# Rev_B_Main_Board.net
KiCad netlist of a schematic drawn in EAGLE
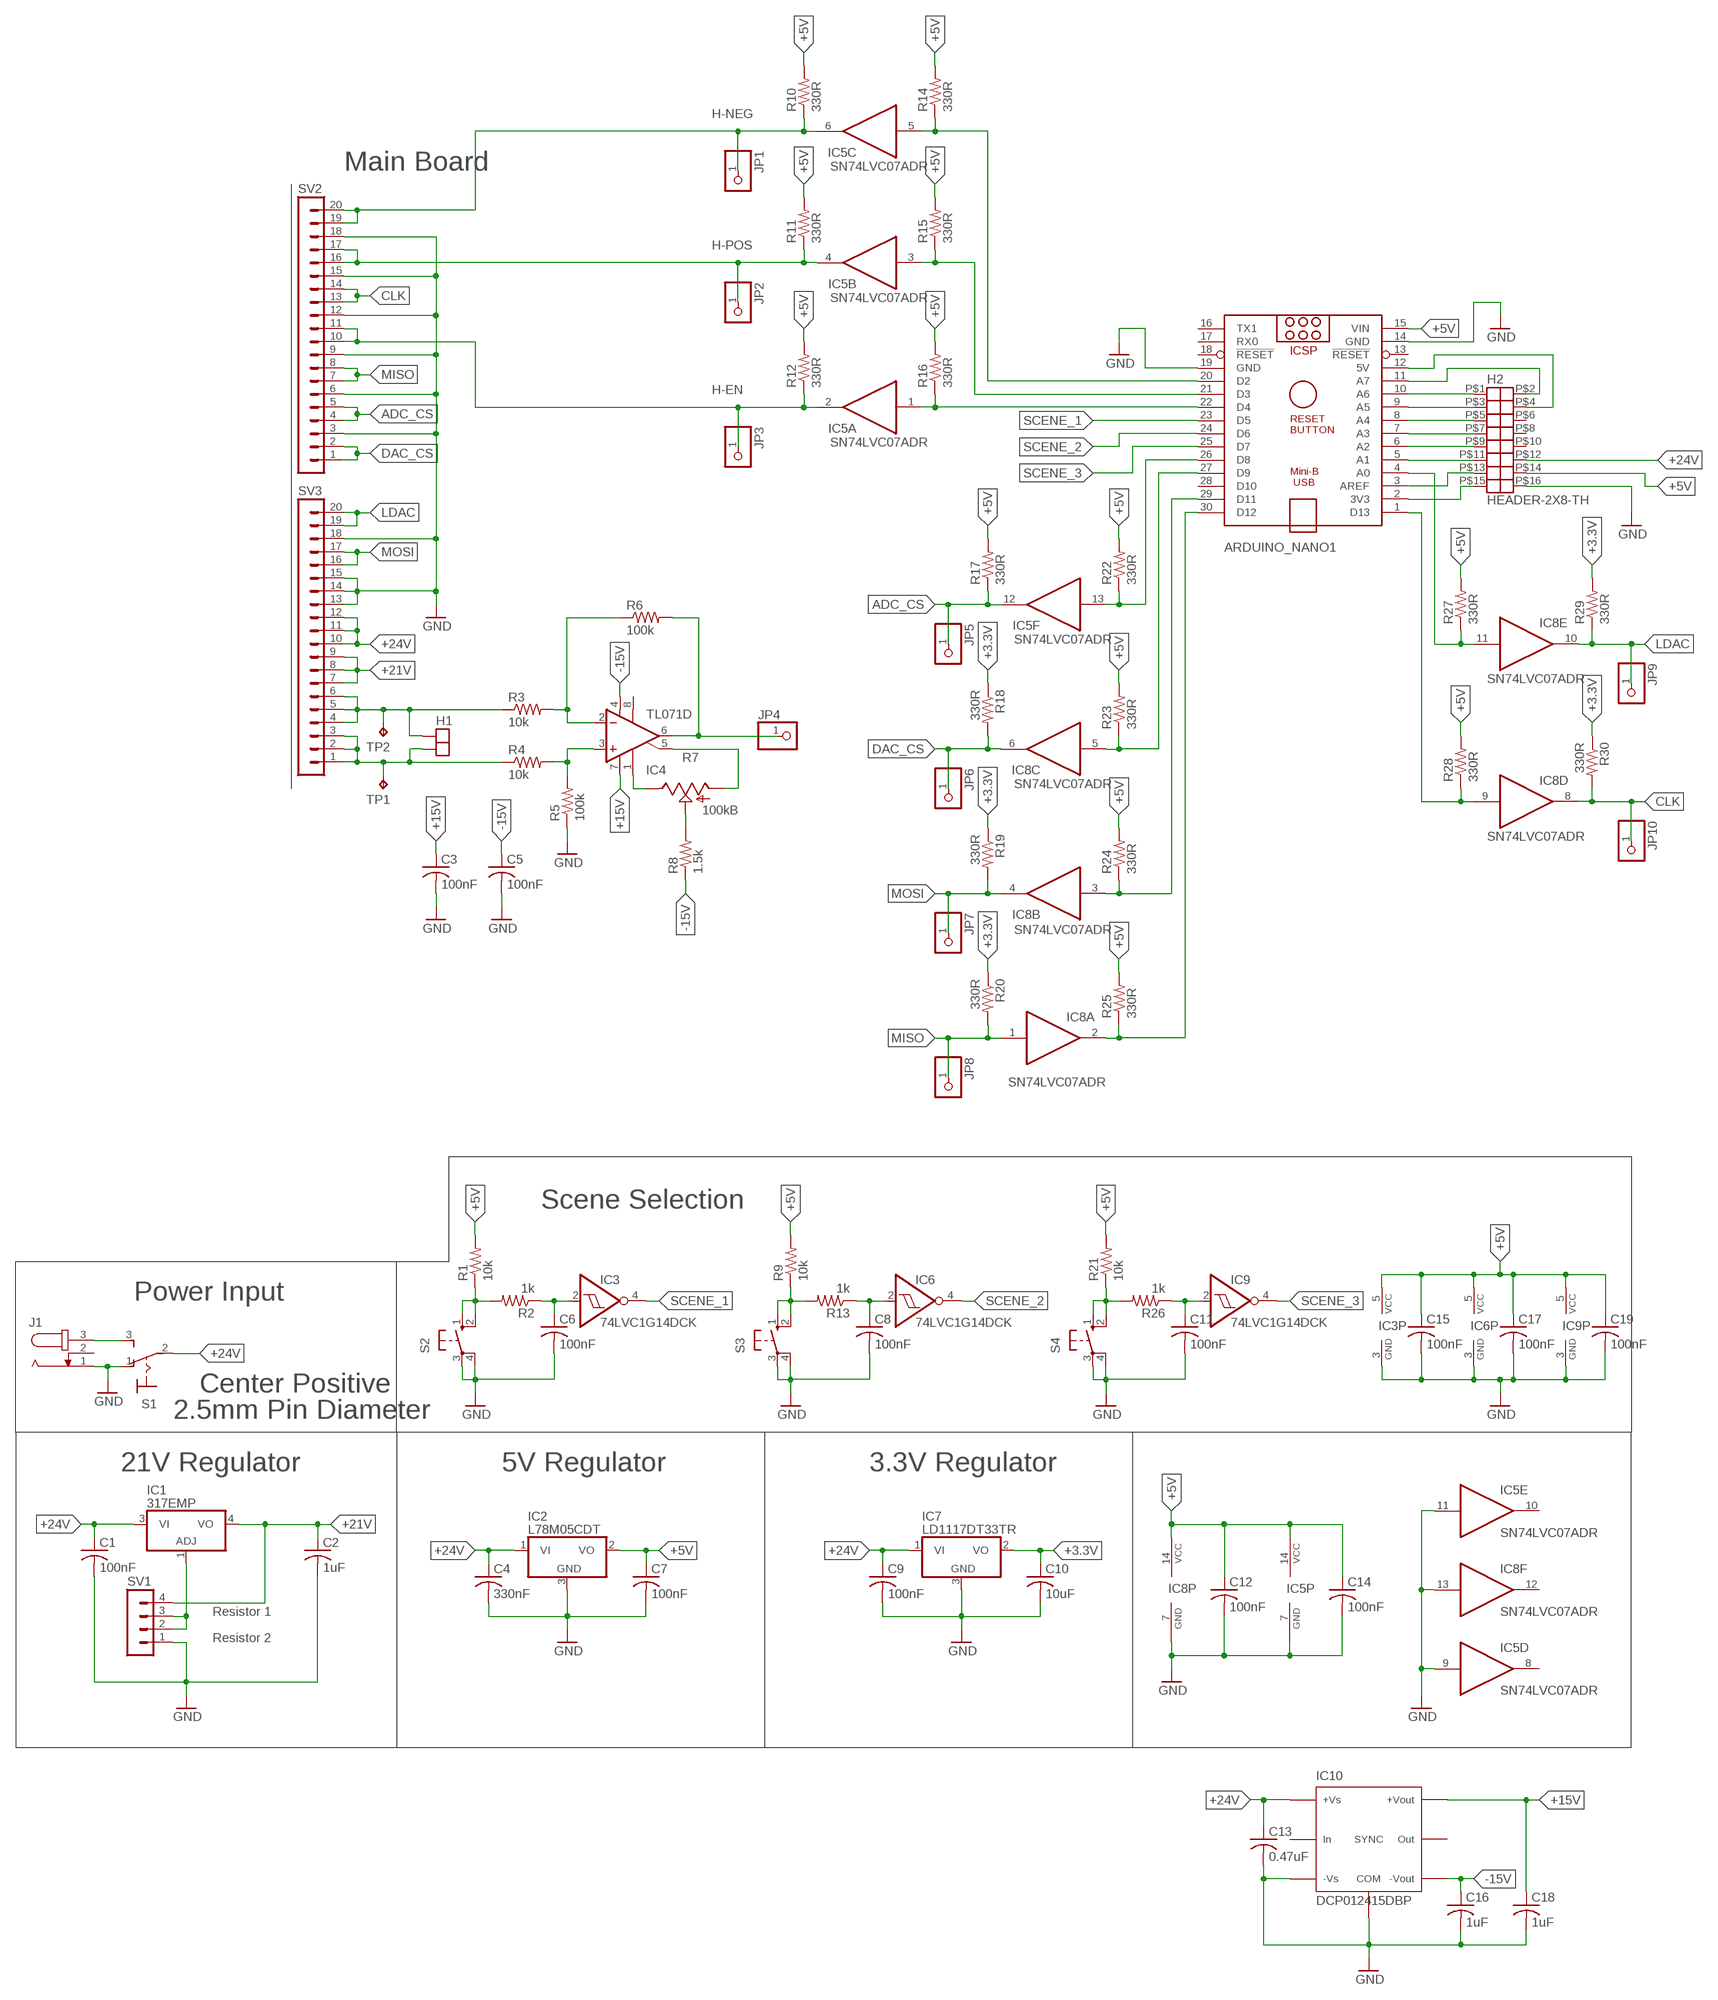
[diagram p0: schematic, sheet 1]

(export (version "E")
  (design (tool "Eeschema 10.0.6"))
  (components
    (comp (ref "ARDUINO_NANO1")
      (value "ARDUINO_NANO")
      (footprint "eagle-import:ARDUINO_NANO")
      (libsource (lib "eagle-import") (part "ARDUINO_NANO"))
    )
    (comp (ref "C1")
      (value "100nF")
      (footprint "eagle-import:C0805")
      (libsource (lib "eagle-import") (part "C-USC0805"))
    )
    (comp (ref "C2")
      (value "1uF")
      (footprint "eagle-import:C0805")
      (libsource (lib "eagle-import") (part "C-USC0805"))
    )
    (comp (ref "C3")
      (value "100nF")
      (footprint "eagle-import:C0805")
      (libsource (lib "eagle-import") (part "C-USC0805"))
    )
    (comp (ref "C4")
      (value "330nF")
      (footprint "eagle-import:C0805")
      (libsource (lib "eagle-import") (part "C-USC0805"))
    )
    (comp (ref "C5")
      (value "100nF")
      (footprint "eagle-import:C0805")
      (libsource (lib "eagle-import") (part "C-USC0805"))
    )
    (comp (ref "C6")
      (value "100nF")
      (footprint "eagle-import:C0805")
      (libsource (lib "eagle-import") (part "C-USC0805"))
    )
    (comp (ref "C7")
      (value "100nF")
      (footprint "eagle-import:C0805")
      (libsource (lib "eagle-import") (part "C-USC0805"))
    )
    (comp (ref "C8")
      (value "100nF")
      (footprint "eagle-import:C0805")
      (libsource (lib "eagle-import") (part "C-USC0805"))
    )
    (comp (ref "C9")
      (value "100nF")
      (footprint "eagle-import:C0805")
      (libsource (lib "eagle-import") (part "C-USC0805"))
    )
    (comp (ref "C10")
      (value "10uF")
      (footprint "eagle-import:C0805")
      (libsource (lib "eagle-import") (part "C-USC0805"))
    )
    (comp (ref "C11")
      (value "100nF")
      (footprint "eagle-import:C0805")
      (libsource (lib "eagle-import") (part "C-USC0805"))
    )
    (comp (ref "C12")
      (value "100nF")
      (footprint "eagle-import:C0805")
      (libsource (lib "eagle-import") (part "C-USC0805"))
    )
    (comp (ref "C13")
      (value "0.47uF")
      (footprint "eagle-import:C0805")
      (libsource (lib "eagle-import") (part "C-USC0805"))
    )
    (comp (ref "C14")
      (value "100nF")
      (footprint "eagle-import:C0805")
      (libsource (lib "eagle-import") (part "C-USC0805"))
    )
    (comp (ref "C15")
      (value "100nF")
      (footprint "eagle-import:C0805")
      (libsource (lib "eagle-import") (part "C-USC0805"))
    )
    (comp (ref "C16")
      (value "1uF")
      (footprint "eagle-import:C0805")
      (libsource (lib "eagle-import") (part "C-USC0805"))
    )
    (comp (ref "C17")
      (value "100nF")
      (footprint "eagle-import:C0805")
      (libsource (lib "eagle-import") (part "C-USC0805"))
    )
    (comp (ref "C18")
      (value "1uF")
      (footprint "eagle-import:C0805")
      (libsource (lib "eagle-import") (part "C-USC0805"))
    )
    (comp (ref "C19")
      (value "100nF")
      (footprint "eagle-import:C0805")
      (libsource (lib "eagle-import") (part "C-USC0805"))
    )
    (comp (ref "H1")
      (value "HEADER-1X2")
      (footprint "eagle-import:HEADER-1X2-TH")
      (libsource (lib "eagle-import") (part "HEADER-1X2"))
    )
    (comp (ref "H2")
      (value "HEADER-2X8-TH")
      (footprint "eagle-import:HEADER-2X8-TH")
      (libsource (lib "eagle-import") (part "HEADER-2X8-TH"))
    )
    (comp (ref "IC1")
      (value "317EMP")
      (footprint "eagle-import:SOT223")
      (libsource (lib "eagle-import") (part "317EMP"))
    )
    (comp (ref "IC2")
      (value "L78M05CDT")
      (footprint "eagle-import:TO252")
      (libsource (lib "eagle-import") (part "78DT18"))
    )
    (comp (ref "IC3")
      (value "74LVC1G14DCK")
      (footprint "eagle-import:SC70-5")
      (libsource (lib "eagle-import") (part "741G14DCKLVC"))
    )
    (comp (ref "IC4")
      (value "TL071D")
      (footprint "eagle-import:SO08")
      (libsource (lib "eagle-import") (part "TL071D"))
    )
    (comp (ref "IC5")
      (value "SN74LVC07ADR")
      (footprint "eagle-import:SO14")
      (libsource (lib "eagle-import") (part "7407DLS"))
    )
    (comp (ref "IC6")
      (value "74LVC1G14DCK")
      (footprint "eagle-import:SC70-5")
      (libsource (lib "eagle-import") (part "741G14DCKLVC"))
    )
    (comp (ref "IC7")
      (value "LD1117DT33TR")
      (footprint "eagle-import:TO252")
      (libsource (lib "eagle-import") (part "78DT18"))
    )
    (comp (ref "IC8")
      (value "SN74LVC07ADR")
      (footprint "eagle-import:SO14")
      (libsource (lib "eagle-import") (part "7407DLS"))
    )
    (comp (ref "IC9")
      (value "74LVC1G14DCK")
      (footprint "eagle-import:SC70-5")
      (libsource (lib "eagle-import") (part "741G14DCKLVC"))
    )
    (comp (ref "IC10")
      (value "DCP012415DBP")
      (footprint "eagle-import:7-PDIP")
      (libsource (lib "eagle-import") (part "DCP012415DBP"))
    )
    (comp (ref "J1")
      (value "JACK-PLUG1")
      (footprint "eagle-import:SPC4078")
      (libsource (lib "eagle-import") (part "JACK-PLUG1"))
    )
    (comp (ref "JP1")
      (value "PINHD-1X1")
      (footprint "eagle-import:1X01")
      (libsource (lib "eagle-import") (part "PINHD-1X1"))
    )
    (comp (ref "JP2")
      (value "PINHD-1X1")
      (footprint "eagle-import:1X01")
      (libsource (lib "eagle-import") (part "PINHD-1X1"))
    )
    (comp (ref "JP3")
      (value "PINHD-1X1")
      (footprint "eagle-import:1X01")
      (libsource (lib "eagle-import") (part "PINHD-1X1"))
    )
    (comp (ref "JP4")
      (value "PINHD-1X1")
      (footprint "eagle-import:1X01")
      (libsource (lib "eagle-import") (part "PINHD-1X1"))
    )
    (comp (ref "JP5")
      (value "PINHD-1X1")
      (footprint "eagle-import:1X01")
      (libsource (lib "eagle-import") (part "PINHD-1X1"))
    )
    (comp (ref "JP6")
      (value "PINHD-1X1")
      (footprint "eagle-import:1X01")
      (libsource (lib "eagle-import") (part "PINHD-1X1"))
    )
    (comp (ref "JP7")
      (value "PINHD-1X1")
      (footprint "eagle-import:1X01")
      (libsource (lib "eagle-import") (part "PINHD-1X1"))
    )
    (comp (ref "JP8")
      (value "PINHD-1X1")
      (footprint "eagle-import:1X01")
      (libsource (lib "eagle-import") (part "PINHD-1X1"))
    )
    (comp (ref "JP9")
      (value "PINHD-1X1")
      (footprint "eagle-import:1X01")
      (libsource (lib "eagle-import") (part "PINHD-1X1"))
    )
    (comp (ref "JP10")
      (value "PINHD-1X1")
      (footprint "eagle-import:1X01")
      (libsource (lib "eagle-import") (part "PINHD-1X1"))
    )
    (comp (ref "R1")
      (value "10k")
      (footprint "eagle-import:R0805")
      (libsource (lib "eagle-import") (part "R-US_R0805"))
    )
    (comp (ref "R2")
      (value "1k")
      (footprint "eagle-import:R0805")
      (libsource (lib "eagle-import") (part "R-US_R0805"))
    )
    (comp (ref "R3")
      (value "10k")
      (footprint "eagle-import:R0805")
      (libsource (lib "eagle-import") (part "R-US_R0805"))
    )
    (comp (ref "R4")
      (value "10k")
      (footprint "eagle-import:R0805")
      (libsource (lib "eagle-import") (part "R-US_R0805"))
    )
    (comp (ref "R5")
      (value "100k")
      (footprint "eagle-import:R0805")
      (libsource (lib "eagle-import") (part "R-US_R0805"))
    )
    (comp (ref "R6")
      (value "100k")
      (footprint "eagle-import:R0805")
      (libsource (lib "eagle-import") (part "R-US_R0805"))
    )
    (comp (ref "R7")
      (value "100kB")
      (footprint "eagle-import:RJ9W")
      (libsource (lib "eagle-import") (part "TRIM_US-RJ9W"))
    )
    (comp (ref "R8")
      (value "1.5k")
      (footprint "eagle-import:R0805")
      (libsource (lib "eagle-import") (part "R-US_R0805"))
    )
    (comp (ref "R9")
      (value "10k")
      (footprint "eagle-import:R0805")
      (libsource (lib "eagle-import") (part "R-US_R0805"))
    )
    (comp (ref "R10")
      (value "330R")
      (footprint "eagle-import:R0805")
      (libsource (lib "eagle-import") (part "R-US_R0805"))
    )
    (comp (ref "R11")
      (value "330R")
      (footprint "eagle-import:R0805")
      (libsource (lib "eagle-import") (part "R-US_R0805"))
    )
    (comp (ref "R12")
      (value "330R")
      (footprint "eagle-import:R0805")
      (libsource (lib "eagle-import") (part "R-US_R0805"))
    )
    (comp (ref "R13")
      (value "1k")
      (footprint "eagle-import:R0805")
      (libsource (lib "eagle-import") (part "R-US_R0805"))
    )
    (comp (ref "R14")
      (value "330R")
      (footprint "eagle-import:R0805")
      (libsource (lib "eagle-import") (part "R-US_R0805"))
    )
    (comp (ref "R15")
      (value "330R")
      (footprint "eagle-import:R0805")
      (libsource (lib "eagle-import") (part "R-US_R0805"))
    )
    (comp (ref "R16")
      (value "330R")
      (footprint "eagle-import:R0805")
      (libsource (lib "eagle-import") (part "R-US_R0805"))
    )
    (comp (ref "R17")
      (value "330R")
      (footprint "eagle-import:R0805")
      (libsource (lib "eagle-import") (part "R-US_R0805"))
    )
    (comp (ref "R18")
      (value "330R")
      (footprint "eagle-import:R0805")
      (libsource (lib "eagle-import") (part "R-US_R0805"))
    )
    (comp (ref "R19")
      (value "330R")
      (footprint "eagle-import:R0805")
      (libsource (lib "eagle-import") (part "R-US_R0805"))
    )
    (comp (ref "R20")
      (value "330R")
      (footprint "eagle-import:R0805")
      (libsource (lib "eagle-import") (part "R-US_R0805"))
    )
    (comp (ref "R21")
      (value "10k")
      (footprint "eagle-import:R0805")
      (libsource (lib "eagle-import") (part "R-US_R0805"))
    )
    (comp (ref "R22")
      (value "330R")
      (footprint "eagle-import:R0805")
      (libsource (lib "eagle-import") (part "R-US_R0805"))
    )
    (comp (ref "R23")
      (value "330R")
      (footprint "eagle-import:R0805")
      (libsource (lib "eagle-import") (part "R-US_R0805"))
    )
    (comp (ref "R24")
      (value "330R")
      (footprint "eagle-import:R0805")
      (libsource (lib "eagle-import") (part "R-US_R0805"))
    )
    (comp (ref "R25")
      (value "330R")
      (footprint "eagle-import:R0805")
      (libsource (lib "eagle-import") (part "R-US_R0805"))
    )
    (comp (ref "R26")
      (value "1k")
      (footprint "eagle-import:R0805")
      (libsource (lib "eagle-import") (part "R-US_R0805"))
    )
    (comp (ref "R27")
      (value "330R")
      (footprint "eagle-import:R0805")
      (libsource (lib "eagle-import") (part "R-US_R0805"))
    )
    (comp (ref "R28")
      (value "330R")
      (footprint "eagle-import:R0805")
      (libsource (lib "eagle-import") (part "R-US_R0805"))
    )
    (comp (ref "R29")
      (value "330R")
      (footprint "eagle-import:R0805")
      (libsource (lib "eagle-import") (part "R-US_R0805"))
    )
    (comp (ref "R30")
      (value "330R")
      (footprint "eagle-import:R0805")
      (libsource (lib "eagle-import") (part "R-US_R0805"))
    )
    (comp (ref "S1")
      (value "320-916")
      (footprint "eagle-import:320-916")
      (libsource (lib "eagle-import") (part "320-916"))
    )
    (comp (ref "S2")
      (value "10-XX")
      (footprint "eagle-import:B3F-10XX")
      (fields (field (name "MPN") "B3F-1000"))
      (libsource (lib "eagle-import") (part "10-XX"))
    )
    (comp (ref "S3")
      (value "10-XX")
      (footprint "eagle-import:B3F-10XX")
      (fields (field (name "MPN") "B3F-1000"))
      (libsource (lib "eagle-import") (part "10-XX"))
    )
    (comp (ref "S4")
      (value "10-XX")
      (footprint "eagle-import:B3F-10XX")
      (fields (field (name "MPN") "B3F-1000"))
      (libsource (lib "eagle-import") (part "10-XX"))
    )
    (comp (ref "SV1")
      (value "MA04-1")
      (footprint "eagle-import:MA04-1")
      (libsource (lib "eagle-import") (part "MA04-1"))
    )
    (comp (ref "SV2")
      (value "MA20-1W")
      (footprint "eagle-import:MA20-1W")
      (libsource (lib "eagle-import") (part "MA20-1W"))
    )
    (comp (ref "SV3")
      (value "MA20-1W")
      (footprint "eagle-import:MA20-1W")
      (libsource (lib "eagle-import") (part "MA20-1W"))
    )
    (comp (ref "TP1")
      (value "TPB2,54")
      (footprint "eagle-import:B2,54")
      (libsource (lib "eagle-import") (part "TPB2,54"))
    )
    (comp (ref "TP2")
      (value "TPB2,54")
      (footprint "eagle-import:B2,54")
      (libsource (lib "eagle-import") (part "TPB2,54"))
    )
  )
  (nets
    (net (code "1") (name "+3.3V") (class "Default")
      (node (ref "C10") (pin "1") (pinfunction "1_1") (pintype "passive"))
      (node (ref "IC7") (pin "2") (pinfunction "VO_2") (pintype "passive"))
      (node (ref "R18") (pin "1") (pinfunction "1_1") (pintype "passive"))
      (node (ref "R19") (pin "1") (pinfunction "1_1") (pintype "passive"))
      (node (ref "R20") (pin "1") (pinfunction "1_1") (pintype "passive"))
      (node (ref "R29") (pin "2") (pinfunction "2_2") (pintype "passive"))
      (node (ref "R30") (pin "1") (pinfunction "1_1") (pintype "passive"))
    )
    (net (code "2") (name "+5V") (class "Default")
      (node (ref "ARDUINO_NANO1") (pin "15") (pinfunction "VIN_15") (pintype "power_in"))
      (node (ref "C12") (pin "1") (pinfunction "1_1") (pintype "passive"))
      (node (ref "C14") (pin "1") (pinfunction "1_1") (pintype "passive"))
      (node (ref "C15") (pin "1") (pinfunction "1_1") (pintype "passive"))
      (node (ref "C17") (pin "1") (pinfunction "1_1") (pintype "passive"))
      (node (ref "C19") (pin "1") (pinfunction "1_1") (pintype "passive"))
      (node (ref "C7") (pin "1") (pinfunction "1_1") (pintype "passive"))
      (node (ref "H2") (pin "P$14") (pinfunction "P$14_P$14") (pintype "bidirectional"))
      (node (ref "IC2") (pin "2") (pinfunction "VO_2") (pintype "passive"))
      (node (ref "IC3") (pin "5") (pinfunction "VCC_5") (pintype "power_in"))
      (node (ref "IC5") (pin "14") (pinfunction "VCC_14") (pintype "power_in"))
      (node (ref "IC6") (pin "5") (pinfunction "VCC_5") (pintype "power_in"))
      (node (ref "IC8") (pin "14") (pinfunction "VCC_14") (pintype "power_in"))
      (node (ref "IC9") (pin "5") (pinfunction "VCC_5") (pintype "power_in"))
      (node (ref "R1") (pin "2") (pinfunction "2_2") (pintype "passive"))
      (node (ref "R10") (pin "2") (pinfunction "2_2") (pintype "passive"))
      (node (ref "R11") (pin "2") (pinfunction "2_2") (pintype "passive"))
      (node (ref "R12") (pin "2") (pinfunction "2_2") (pintype "passive"))
      (node (ref "R14") (pin "2") (pinfunction "2_2") (pintype "passive"))
      (node (ref "R15") (pin "2") (pinfunction "2_2") (pintype "passive"))
      (node (ref "R16") (pin "2") (pinfunction "2_2") (pintype "passive"))
      (node (ref "R17") (pin "2") (pinfunction "2_2") (pintype "passive"))
      (node (ref "R21") (pin "2") (pinfunction "2_2") (pintype "passive"))
      (node (ref "R22") (pin "2") (pinfunction "2_2") (pintype "passive"))
      (node (ref "R23") (pin "2") (pinfunction "2_2") (pintype "passive"))
      (node (ref "R24") (pin "2") (pinfunction "2_2") (pintype "passive"))
      (node (ref "R25") (pin "2") (pinfunction "2_2") (pintype "passive"))
      (node (ref "R27") (pin "2") (pinfunction "2_2") (pintype "passive"))
      (node (ref "R28") (pin "2") (pinfunction "2_2") (pintype "passive"))
      (node (ref "R9") (pin "2") (pinfunction "2_2") (pintype "passive"))
    )
    (net (code "3") (name "+15V") (class "Default")
      (node (ref "C18") (pin "1") (pinfunction "1_1") (pintype "passive"))
      (node (ref "C3") (pin "1") (pinfunction "1_1") (pintype "passive"))
      (node (ref "IC10") (pin "P$4") (pinfunction "P$4_P$4") (pintype "bidirectional"))
      (node (ref "IC4") (pin "7") (pinfunction "V+_7") (pintype "power_in"))
    )
    (net (code "4") (name "+21V") (class "Default")
      (node (ref "C2") (pin "1") (pinfunction "1_1") (pintype "passive"))
      (node (ref "IC1") (pin "4") (pinfunction "VO_4") (pintype "passive"))
      (node (ref "SV1") (pin "4") (pinfunction "4_4") (pintype "passive"))
      (node (ref "SV3") (pin "7") (pinfunction "7_7") (pintype "passive"))
      (node (ref "SV3") (pin "8") (pinfunction "8_8") (pintype "passive"))
      (node (ref "SV3") (pin "9") (pinfunction "9_9") (pintype "passive"))
    )
    (net (code "5") (name "+24V") (class "Default")
      (node (ref "C1") (pin "1") (pinfunction "1_1") (pintype "passive"))
      (node (ref "C13") (pin "1") (pinfunction "1_1") (pintype "passive"))
      (node (ref "C4") (pin "1") (pinfunction "1_1") (pintype "passive"))
      (node (ref "C9") (pin "1") (pinfunction "1_1") (pintype "passive"))
      (node (ref "H2") (pin "P$12") (pinfunction "P$12_P$12") (pintype "bidirectional"))
      (node (ref "IC1") (pin "3") (pinfunction "VI_3") (pintype "input"))
      (node (ref "IC10") (pin "P$1") (pinfunction "P$1_P$1") (pintype "bidirectional"))
      (node (ref "IC2") (pin "1") (pinfunction "VI_1") (pintype "input"))
      (node (ref "IC7") (pin "1") (pinfunction "VI_1") (pintype "input"))
      (node (ref "S1") (pin "2") (pinfunction "P_2") (pintype "passive"))
      (node (ref "SV3") (pin "10") (pinfunction "10_10") (pintype "passive"))
      (node (ref "SV3") (pin "11") (pinfunction "11_11") (pintype "passive"))
      (node (ref "SV3") (pin "12") (pinfunction "12_12") (pintype "passive"))
    )
    (net (code "6") (name "-15V") (class "Default")
      (node (ref "C16") (pin "1") (pinfunction "1_1") (pintype "passive"))
      (node (ref "C5") (pin "1") (pinfunction "1_1") (pintype "passive"))
      (node (ref "IC10") (pin "P$5") (pinfunction "P$5_P$5") (pintype "bidirectional"))
      (node (ref "IC4") (pin "4") (pinfunction "V-_4") (pintype "power_in"))
      (node (ref "R8") (pin "1") (pinfunction "1_1") (pintype "passive"))
    )
    (net (code "7") (name "ADC_CS") (class "Default")
      (node (ref "IC5") (pin "12") (pinfunction "O_12") (pintype "open_collector"))
      (node (ref "JP5") (pin "1") (pinfunction "1_1") (pintype "passive"))
      (node (ref "R17") (pin "1") (pinfunction "1_1") (pintype "passive"))
      (node (ref "SV2") (pin "4") (pinfunction "4_4") (pintype "passive"))
      (node (ref "SV2") (pin "5") (pinfunction "5_5") (pintype "passive"))
    )
    (net (code "8") (name "CLK") (class "Default")
      (node (ref "IC8") (pin "8") (pinfunction "O_8") (pintype "open_collector"))
      (node (ref "JP10") (pin "1") (pinfunction "1_1") (pintype "passive"))
      (node (ref "R30") (pin "2") (pinfunction "2_2") (pintype "passive"))
      (node (ref "SV2") (pin "13") (pinfunction "13_13") (pintype "passive"))
      (node (ref "SV2") (pin "14") (pinfunction "14_14") (pintype "passive"))
    )
    (net (code "9") (name "DAC_CS") (class "Default")
      (node (ref "IC8") (pin "6") (pinfunction "O_6") (pintype "open_collector"))
      (node (ref "JP6") (pin "1") (pinfunction "1_1") (pintype "passive"))
      (node (ref "R18") (pin "2") (pinfunction "2_2") (pintype "passive"))
      (node (ref "SV2") (pin "1") (pinfunction "1_1") (pintype "passive"))
      (node (ref "SV2") (pin "2") (pinfunction "2_2") (pintype "passive"))
    )
    (net (code "10") (name "GND") (class "Default")
      (node (ref "ARDUINO_NANO1") (pin "14") (pinfunction "GND_14") (pintype "power_in"))
      (node (ref "ARDUINO_NANO1") (pin "19") (pinfunction "GND_19") (pintype "power_in"))
      (node (ref "C1") (pin "2") (pinfunction "2_2") (pintype "passive"))
      (node (ref "C10") (pin "2") (pinfunction "2_2") (pintype "passive"))
      (node (ref "C11") (pin "2") (pinfunction "2_2") (pintype "passive"))
      (node (ref "C12") (pin "2") (pinfunction "2_2") (pintype "passive"))
      (node (ref "C13") (pin "2") (pinfunction "2_2") (pintype "passive"))
      (node (ref "C14") (pin "2") (pinfunction "2_2") (pintype "passive"))
      (node (ref "C15") (pin "2") (pinfunction "2_2") (pintype "passive"))
      (node (ref "C16") (pin "2") (pinfunction "2_2") (pintype "passive"))
      (node (ref "C17") (pin "2") (pinfunction "2_2") (pintype "passive"))
      (node (ref "C18") (pin "2") (pinfunction "2_2") (pintype "passive"))
      (node (ref "C19") (pin "2") (pinfunction "2_2") (pintype "passive"))
      (node (ref "C2") (pin "2") (pinfunction "2_2") (pintype "passive"))
      (node (ref "C3") (pin "2") (pinfunction "2_2") (pintype "passive"))
      (node (ref "C4") (pin "2") (pinfunction "2_2") (pintype "passive"))
      (node (ref "C5") (pin "2") (pinfunction "2_2") (pintype "passive"))
      (node (ref "C6") (pin "2") (pinfunction "2_2") (pintype "passive"))
      (node (ref "C7") (pin "2") (pinfunction "2_2") (pintype "passive"))
      (node (ref "C8") (pin "2") (pinfunction "2_2") (pintype "passive"))
      (node (ref "C9") (pin "2") (pinfunction "2_2") (pintype "passive"))
      (node (ref "H2") (pin "P$16") (pinfunction "P$16_P$16") (pintype "bidirectional"))
      (node (ref "IC10") (pin "P$2") (pinfunction "P$3_P$2") (pintype "bidirectional"))
      (node (ref "IC10") (pin "P$3") (pinfunction "P$7_P$3") (pintype "bidirectional"))
      (node (ref "IC2") (pin "3") (pinfunction "GND_3") (pintype "passive"))
      (node (ref "IC3") (pin "3") (pinfunction "GND_3") (pintype "power_in"))
      (node (ref "IC5") (pin "11") (pinfunction "I_11") (pintype "input"))
      (node (ref "IC5") (pin "7") (pinfunction "GND_7") (pintype "power_in"))
      (node (ref "IC5") (pin "9") (pinfunction "I_9") (pintype "input"))
      (node (ref "IC6") (pin "3") (pinfunction "GND_3") (pintype "power_in"))
      (node (ref "IC7") (pin "3") (pinfunction "GND_3") (pintype "passive"))
      (node (ref "IC8") (pin "13") (pinfunction "I_13") (pintype "input"))
      (node (ref "IC8") (pin "7") (pinfunction "GND_7") (pintype "power_in"))
      (node (ref "IC9") (pin "3") (pinfunction "GND_3") (pintype "power_in"))
      (node (ref "J1") (pin "1") (pinfunction "1_1") (pintype "passive"))
      (node (ref "R5") (pin "1") (pinfunction "1_1") (pintype "passive"))
      (node (ref "S1") (pin "1") (pinfunction "O_1") (pintype "passive"))
      (node (ref "S2") (pin "3") (pinfunction "P_3") (pintype "passive"))
      (node (ref "S2") (pin "4") (pinfunction "P1_4") (pintype "passive"))
      (node (ref "S3") (pin "3") (pinfunction "P_3") (pintype "passive"))
      (node (ref "S3") (pin "4") (pinfunction "P1_4") (pintype "passive"))
      (node (ref "S4") (pin "3") (pinfunction "P_3") (pintype "passive"))
      (node (ref "S4") (pin "4") (pinfunction "P1_4") (pintype "passive"))
      (node (ref "SV1") (pin "1") (pinfunction "1_1") (pintype "passive"))
      (node (ref "SV2") (pin "12") (pinfunction "12_12") (pintype "passive"))
      (node (ref "SV2") (pin "15") (pinfunction "15_15") (pintype "passive"))
      (node (ref "SV2") (pin "18") (pinfunction "18_18") (pintype "passive"))
      (node (ref "SV2") (pin "3") (pinfunction "3_3") (pintype "passive"))
      (node (ref "SV2") (pin "6") (pinfunction "6_6") (pintype "passive"))
      (node (ref "SV2") (pin "9") (pinfunction "9_9") (pintype "passive"))
      (node (ref "SV3") (pin "13") (pinfunction "13_13") (pintype "passive"))
      (node (ref "SV3") (pin "14") (pinfunction "14_14") (pintype "passive"))
      (node (ref "SV3") (pin "15") (pinfunction "15_15") (pintype "passive"))
      (node (ref "SV3") (pin "18") (pinfunction "18_18") (pintype "passive"))
    )
    (net (code "11") (name "LDAC") (class "Default")
      (node (ref "IC8") (pin "10") (pinfunction "O_10") (pintype "open_collector"))
      (node (ref "JP9") (pin "1") (pinfunction "1_1") (pintype "passive"))
      (node (ref "R29") (pin "1") (pinfunction "1_1") (pintype "passive"))
      (node (ref "SV3") (pin "19") (pinfunction "19_19") (pintype "passive"))
      (node (ref "SV3") (pin "20") (pinfunction "20_20") (pintype "passive"))
    )
    (net (code "12") (name "MISO") (class "Default")
      (node (ref "IC8") (pin "1") (pinfunction "I_1") (pintype "input"))
      (node (ref "JP8") (pin "1") (pinfunction "1_1") (pintype "passive"))
      (node (ref "R20") (pin "2") (pinfunction "2_2") (pintype "passive"))
      (node (ref "SV2") (pin "7") (pinfunction "7_7") (pintype "passive"))
      (node (ref "SV2") (pin "8") (pinfunction "8_8") (pintype "passive"))
    )
    (net (code "13") (name "MOSI") (class "Default")
      (node (ref "IC8") (pin "4") (pinfunction "O_4") (pintype "open_collector"))
      (node (ref "JP7") (pin "1") (pinfunction "1_1") (pintype "passive"))
      (node (ref "R19") (pin "2") (pinfunction "2_2") (pintype "passive"))
      (node (ref "SV3") (pin "16") (pinfunction "16_16") (pintype "passive"))
      (node (ref "SV3") (pin "17") (pinfunction "17_17") (pintype "passive"))
    )
    (net (code "14") (name "Net-(ARDUINO_NANO1-3V3)") (class "Default")
      (node (ref "ARDUINO_NANO1") (pin "2") (pinfunction "3V3_2") (pintype "output"))
      (node (ref "H2") (pin "P$15") (pinfunction "P$15_P$15") (pintype "bidirectional"))
    )
    (net (code "15") (name "Net-(ARDUINO_NANO1-5V)") (class "Default")
      (node (ref "ARDUINO_NANO1") (pin "12") (pinfunction "5V_12") (pintype "power_in"))
      (node (ref "H2") (pin "P$4") (pinfunction "P$4_P$4") (pintype "bidirectional"))
    )
    (net (code "16") (name "Net-(ARDUINO_NANO1-A0)") (class "Default")
      (node (ref "ARDUINO_NANO1") (pin "4") (pinfunction "A0_4") (pintype "bidirectional"))
      (node (ref "IC8") (pin "11") (pinfunction "I_11") (pintype "input"))
      (node (ref "R27") (pin "1") (pinfunction "1_1") (pintype "passive"))
    )
    (net (code "17") (name "Net-(ARDUINO_NANO1-A1)") (class "Default")
      (node (ref "ARDUINO_NANO1") (pin "5") (pinfunction "A1_5") (pintype "bidirectional"))
      (node (ref "H2") (pin "P$11") (pinfunction "P$11_P$11") (pintype "bidirectional"))
    )
    (net (code "18") (name "Net-(ARDUINO_NANO1-A2)") (class "Default")
      (node (ref "ARDUINO_NANO1") (pin "6") (pinfunction "A2_6") (pintype "bidirectional"))
      (node (ref "H2") (pin "P$9") (pinfunction "P$9_P$9") (pintype "bidirectional"))
    )
    (net (code "19") (name "Net-(ARDUINO_NANO1-A3)") (class "Default")
      (node (ref "ARDUINO_NANO1") (pin "7") (pinfunction "A3_7") (pintype "bidirectional"))
      (node (ref "H2") (pin "P$7") (pinfunction "P$7_P$7") (pintype "bidirectional"))
    )
    (net (code "20") (name "Net-(ARDUINO_NANO1-A4)") (class "Default")
      (node (ref "ARDUINO_NANO1") (pin "8") (pinfunction "A4_8") (pintype "bidirectional"))
      (node (ref "H2") (pin "P$5") (pinfunction "P$5_P$5") (pintype "bidirectional"))
    )
    (net (code "21") (name "Net-(ARDUINO_NANO1-A5)") (class "Default")
      (node (ref "ARDUINO_NANO1") (pin "9") (pinfunction "A5_9") (pintype "bidirectional"))
      (node (ref "H2") (pin "P$3") (pinfunction "P$3_P$3") (pintype "bidirectional"))
    )
    (net (code "22") (name "Net-(ARDUINO_NANO1-A6)") (class "Default")
      (node (ref "ARDUINO_NANO1") (pin "10") (pinfunction "A6_10") (pintype "bidirectional"))
      (node (ref "H2") (pin "P$1") (pinfunction "P$1_P$1") (pintype "bidirectional"))
    )
    (net (code "23") (name "Net-(ARDUINO_NANO1-A7)") (class "Default")
      (node (ref "ARDUINO_NANO1") (pin "11") (pinfunction "A7_11") (pintype "bidirectional"))
      (node (ref "H2") (pin "P$2") (pinfunction "P$2_P$2") (pintype "bidirectional"))
    )
    (net (code "24") (name "Net-(ARDUINO_NANO1-AREF)") (class "Default")
      (node (ref "ARDUINO_NANO1") (pin "3") (pinfunction "AREF_3") (pintype "input"))
      (node (ref "H2") (pin "P$13") (pinfunction "P$13_P$13") (pintype "bidirectional"))
    )
    (net (code "25") (name "Net-(ARDUINO_NANO1-D2)") (class "Default")
      (node (ref "ARDUINO_NANO1") (pin "20") (pinfunction "D2_20") (pintype "bidirectional"))
      (node (ref "IC5") (pin "5") (pinfunction "I_5") (pintype "input"))
      (node (ref "R14") (pin "1") (pinfunction "1_1") (pintype "passive"))
    )
    (net (code "26") (name "Net-(ARDUINO_NANO1-D3)") (class "Default")
      (node (ref "ARDUINO_NANO1") (pin "21") (pinfunction "D3_21") (pintype "bidirectional"))
      (node (ref "IC5") (pin "3") (pinfunction "I_3") (pintype "input"))
      (node (ref "R15") (pin "1") (pinfunction "1_1") (pintype "passive"))
    )
    (net (code "27") (name "Net-(ARDUINO_NANO1-D4)") (class "Default")
      (node (ref "ARDUINO_NANO1") (pin "22") (pinfunction "D4_22") (pintype "bidirectional"))
      (node (ref "IC5") (pin "1") (pinfunction "I_1") (pintype "input"))
      (node (ref "R16") (pin "1") (pinfunction "1_1") (pintype "passive"))
    )
    (net (code "28") (name "Net-(ARDUINO_NANO1-D8)") (class "Default")
      (node (ref "ARDUINO_NANO1") (pin "26") (pinfunction "D8_26") (pintype "bidirectional"))
      (node (ref "IC5") (pin "13") (pinfunction "I_13") (pintype "input"))
      (node (ref "R22") (pin "1") (pinfunction "1_1") (pintype "passive"))
    )
    (net (code "29") (name "Net-(ARDUINO_NANO1-D9)") (class "Default")
      (node (ref "ARDUINO_NANO1") (pin "27") (pinfunction "D9_27") (pintype "bidirectional"))
      (node (ref "IC8") (pin "5") (pinfunction "I_5") (pintype "input"))
      (node (ref "R23") (pin "1") (pinfunction "1_1") (pintype "passive"))
    )
    (net (code "30") (name "Net-(ARDUINO_NANO1-D11)") (class "Default")
      (node (ref "ARDUINO_NANO1") (pin "29") (pinfunction "D11_29") (pintype "bidirectional"))
      (node (ref "IC8") (pin "3") (pinfunction "I_3") (pintype "input"))
      (node (ref "R24") (pin "1") (pinfunction "1_1") (pintype "passive"))
    )
    (net (code "31") (name "Net-(ARDUINO_NANO1-D12)") (class "Default")
      (node (ref "ARDUINO_NANO1") (pin "30") (pinfunction "D12_30") (pintype "bidirectional"))
      (node (ref "IC8") (pin "2") (pinfunction "O_2") (pintype "open_collector"))
      (node (ref "R25") (pin "1") (pinfunction "1_1") (pintype "passive"))
    )
    (net (code "32") (name "Net-(ARDUINO_NANO1-D13)") (class "Default")
      (node (ref "ARDUINO_NANO1") (pin "1") (pinfunction "D13_1") (pintype "bidirectional"))
      (node (ref "IC8") (pin "9") (pinfunction "I_9") (pintype "input"))
      (node (ref "R28") (pin "1") (pinfunction "1_1") (pintype "passive"))
    )
    (net (code "33") (name "Net-(H1-PadP$1)") (class "Default")
      (node (ref "H1") (pin "P$1") (pinfunction "P$1_P$1") (pintype "bidirectional"))
      (node (ref "R3") (pin "1") (pinfunction "1_1") (pintype "passive"))
      (node (ref "SV3") (pin "4") (pinfunction "4_4") (pintype "passive"))
      (node (ref "SV3") (pin "5") (pinfunction "5_5") (pintype "passive"))
      (node (ref "SV3") (pin "6") (pinfunction "6_6") (pintype "passive"))
      (node (ref "TP2") (pin "TP") (pinfunction "TP_TP") (pintype "input"))
    )
    (net (code "34") (name "Net-(H1-PadP$2)") (class "Default")
      (node (ref "H1") (pin "P$2") (pinfunction "P$2_P$2") (pintype "bidirectional"))
      (node (ref "R4") (pin "1") (pinfunction "1_1") (pintype "passive"))
      (node (ref "SV3") (pin "1") (pinfunction "1_1") (pintype "passive"))
      (node (ref "SV3") (pin "2") (pinfunction "2_2") (pintype "passive"))
      (node (ref "SV3") (pin "3") (pinfunction "3_3") (pintype "passive"))
      (node (ref "TP1") (pin "TP") (pinfunction "TP_TP") (pintype "input"))
    )
    (net (code "35") (name "Net-(IC1-ADJ)") (class "Default")
      (node (ref "IC1") (pin "1") (pinfunction "ADJ_1") (pintype "input"))
      (node (ref "SV1") (pin "2") (pinfunction "2_2") (pintype "passive"))
      (node (ref "SV1") (pin "3") (pinfunction "3_3") (pintype "passive"))
    )
    (net (code "36") (name "Net-(IC3A-I)") (class "Default")
      (node (ref "C6") (pin "1") (pinfunction "1_1") (pintype "passive"))
      (node (ref "IC3") (pin "2") (pinfunction "I_2") (pintype "input"))
      (node (ref "R2") (pin "1") (pinfunction "1_1") (pintype "passive"))
    )
    (net (code "37") (name "Net-(IC4-+IN)") (class "Default")
      (node (ref "IC4") (pin "3") (pinfunction "+IN_3") (pintype "input"))
      (node (ref "R4") (pin "2") (pinfunction "2_2") (pintype "passive"))
      (node (ref "R5") (pin "2") (pinfunction "2_2") (pintype "passive"))
    )
    (net (code "38") (name "Net-(IC4--IN)") (class "Default")
      (node (ref "IC4") (pin "2") (pinfunction "-IN_2") (pintype "input"))
      (node (ref "R3") (pin "2") (pinfunction "2_2") (pintype "passive"))
      (node (ref "R6") (pin "1") (pinfunction "1_1") (pintype "passive"))
    )
    (net (code "39") (name "Net-(IC4-ON1)") (class "Default")
      (node (ref "IC4") (pin "1") (pinfunction "ON1_1") (pintype "passive"))
      (node (ref "R7") (pin "E") (pinfunction "E_E") (pintype "passive"))
    )
    (net (code "40") (name "Net-(IC4-ON2)") (class "Default")
      (node (ref "IC4") (pin "5") (pinfunction "ON2_5") (pintype "passive"))
      (node (ref "R7") (pin "A") (pinfunction "A_A") (pintype "passive"))
    )
    (net (code "41") (name "Net-(IC4-OUT)") (class "Default")
      (node (ref "IC4") (pin "6") (pinfunction "OUT_6") (pintype "output"))
      (node (ref "JP4") (pin "1") (pinfunction "1_1") (pintype "passive"))
      (node (ref "R6") (pin "2") (pinfunction "2_2") (pintype "passive"))
    )
    (net (code "42") (name "Net-(IC5A-O)") (class "Default")
      (node (ref "IC5") (pin "2") (pinfunction "O_2") (pintype "open_collector"))
      (node (ref "JP3") (pin "1") (pinfunction "1_1") (pintype "passive"))
      (node (ref "R12") (pin "1") (pinfunction "1_1") (pintype "passive"))
      (node (ref "SV2") (pin "10") (pinfunction "10_10") (pintype "passive"))
      (node (ref "SV2") (pin "11") (pinfunction "11_11") (pintype "passive"))
    )
    (net (code "43") (name "Net-(IC5B-O)") (class "Default")
      (node (ref "IC5") (pin "4") (pinfunction "O_4") (pintype "open_collector"))
      (node (ref "JP2") (pin "1") (pinfunction "1_1") (pintype "passive"))
      (node (ref "R11") (pin "1") (pinfunction "1_1") (pintype "passive"))
      (node (ref "SV2") (pin "16") (pinfunction "16_16") (pintype "passive"))
      (node (ref "SV2") (pin "17") (pinfunction "17_17") (pintype "passive"))
    )
    (net (code "44") (name "Net-(IC5C-O)") (class "Default")
      (node (ref "IC5") (pin "6") (pinfunction "O_6") (pintype "open_collector"))
      (node (ref "JP1") (pin "1") (pinfunction "1_1") (pintype "passive"))
      (node (ref "R10") (pin "1") (pinfunction "1_1") (pintype "passive"))
      (node (ref "SV2") (pin "19") (pinfunction "19_19") (pintype "passive"))
      (node (ref "SV2") (pin "20") (pinfunction "20_20") (pintype "passive"))
    )
    (net (code "45") (name "Net-(IC6A-I)") (class "Default")
      (node (ref "C8") (pin "1") (pinfunction "1_1") (pintype "passive"))
      (node (ref "IC6") (pin "2") (pinfunction "I_2") (pintype "input"))
      (node (ref "R13") (pin "1") (pinfunction "1_1") (pintype "passive"))
    )
    (net (code "46") (name "Net-(IC9A-I)") (class "Default")
      (node (ref "C11") (pin "1") (pinfunction "1_1") (pintype "passive"))
      (node (ref "IC9") (pin "2") (pinfunction "I_2") (pintype "input"))
      (node (ref "R26") (pin "1") (pinfunction "1_1") (pintype "passive"))
    )
    (net (code "47") (name "Net-(R7-PadS)") (class "Default")
      (node (ref "R7") (pin "S") (pinfunction "S_S") (pintype "passive"))
      (node (ref "R8") (pin "2") (pinfunction "2_2") (pintype "passive"))
    )
    (net (code "48") (name "Net-(S1-S)") (class "Default")
      (node (ref "J1") (pin "3") (pinfunction "3_3") (pintype "passive"))
      (node (ref "S1") (pin "3") (pinfunction "S_3") (pintype "passive"))
    )
    (net (code "49") (name "Net-(S2-S)") (class "Default")
      (node (ref "R1") (pin "1") (pinfunction "1_1") (pintype "passive"))
      (node (ref "R2") (pin "2") (pinfunction "2_2") (pintype "passive"))
      (node (ref "S2") (pin "1") (pinfunction "S_1") (pintype "passive"))
      (node (ref "S2") (pin "2") (pinfunction "S1_2") (pintype "passive"))
    )
    (net (code "50") (name "Net-(S3-S)") (class "Default")
      (node (ref "R13") (pin "2") (pinfunction "2_2") (pintype "passive"))
      (node (ref "R9") (pin "1") (pinfunction "1_1") (pintype "passive"))
      (node (ref "S3") (pin "1") (pinfunction "S_1") (pintype "passive"))
      (node (ref "S3") (pin "2") (pinfunction "S1_2") (pintype "passive"))
    )
    (net (code "51") (name "Net-(S4-S)") (class "Default")
      (node (ref "R21") (pin "1") (pinfunction "1_1") (pintype "passive"))
      (node (ref "R26") (pin "2") (pinfunction "2_2") (pintype "passive"))
      (node (ref "S4") (pin "1") (pinfunction "S_1") (pintype "passive"))
      (node (ref "S4") (pin "2") (pinfunction "S1_2") (pintype "passive"))
    )
    (net (code "52") (name "SCENE_1") (class "Default")
      (node (ref "ARDUINO_NANO1") (pin "23") (pinfunction "D5_23") (pintype "bidirectional"))
      (node (ref "IC3") (pin "4") (pinfunction "O_4") (pintype "output"))
    )
    (net (code "53") (name "SCENE_2") (class "Default")
      (node (ref "ARDUINO_NANO1") (pin "24") (pinfunction "D6_24") (pintype "bidirectional"))
      (node (ref "IC6") (pin "4") (pinfunction "O_4") (pintype "output"))
    )
    (net (code "54") (name "SCENE_3") (class "Default")
      (node (ref "ARDUINO_NANO1") (pin "25") (pinfunction "D7_25") (pintype "bidirectional"))
      (node (ref "IC9") (pin "4") (pinfunction "O_4") (pintype "output"))
    )
    (net (code "55") (name "unconnected-(ARDUINO_NANO1-D10-Pad28)") (class "Default")
      (node (ref "ARDUINO_NANO1") (pin "28") (pinfunction "D10_28") (pintype "bidirectional"))
    )
    (net (code "56") (name "unconnected-(ARDUINO_NANO1-RX0-Pad17)") (class "Default")
      (node (ref "ARDUINO_NANO1") (pin "17") (pinfunction "RX0_17") (pintype "bidirectional"))
    )
    (net (code "57") (name "unconnected-(ARDUINO_NANO1-TX1-Pad16)") (class "Default")
      (node (ref "ARDUINO_NANO1") (pin "16") (pinfunction "TX1_16") (pintype "bidirectional"))
    )
    (net (code "58") (name "unconnected-(ARDUINO_NANO1-~{RESET}-Pad13)") (class "Default")
      (node (ref "ARDUINO_NANO1") (pin "13") (pinfunction "~{RESET}_13") (pintype "input"))
    )
    (net (code "59") (name "unconnected-(ARDUINO_NANO1-~{RESET}-Pad18)") (class "Default")
      (node (ref "ARDUINO_NANO1") (pin "18") (pinfunction "~{RESET}_18") (pintype "input"))
    )
    (net (code "60") (name "unconnected-(H2-PadP$6)") (class "Default")
      (node (ref "H2") (pin "P$6") (pinfunction "P$6_P$6") (pintype "bidirectional"))
    )
    (net (code "61") (name "unconnected-(H2-PadP$8)") (class "Default")
      (node (ref "H2") (pin "P$8") (pinfunction "P$8_P$8") (pintype "bidirectional"))
    )
    (net (code "62") (name "unconnected-(H2-PadP$10)") (class "Default")
      (node (ref "H2") (pin "P$10") (pinfunction "P$10_P$10") (pintype "bidirectional"))
    )
    (net (code "63") (name "unconnected-(IC4-OPT-Pad8)") (class "Default")
      (node (ref "IC4") (pin "8") (pinfunction "OPT_8") (pintype "passive"))
    )
    (net (code "64") (name "unconnected-(IC5D-O-Pad8)") (class "Default")
      (node (ref "IC5") (pin "8") (pinfunction "O_8") (pintype "open_collector"))
    )
    (net (code "65") (name "unconnected-(IC5E-O-Pad10)") (class "Default")
      (node (ref "IC5") (pin "10") (pinfunction "O_10") (pintype "open_collector"))
    )
    (net (code "66") (name "unconnected-(IC8F-O-Pad12)") (class "Default")
      (node (ref "IC8") (pin "12") (pinfunction "O_12") (pintype "open_collector"))
    )
    (net (code "67") (name "unconnected-(IC10-P$2-PadP$6)") (class "Default")
      (node (ref "IC10") (pin "P$6") (pinfunction "P$2_P$6") (pintype "bidirectional"))
    )
    (net (code "68") (name "unconnected-(IC10-P$6-PadP$7)") (class "Default")
      (node (ref "IC10") (pin "P$7") (pinfunction "P$6_P$7") (pintype "bidirectional"))
    )
    (net (code "69") (name "unconnected-(J1-Pad2)") (class "Default")
      (node (ref "J1") (pin "2") (pinfunction "2_2") (pintype "passive"))
    )
  )
)
